# inverter-adc-demo.net
KiCad netlist of a schematic drawn in EAGLE
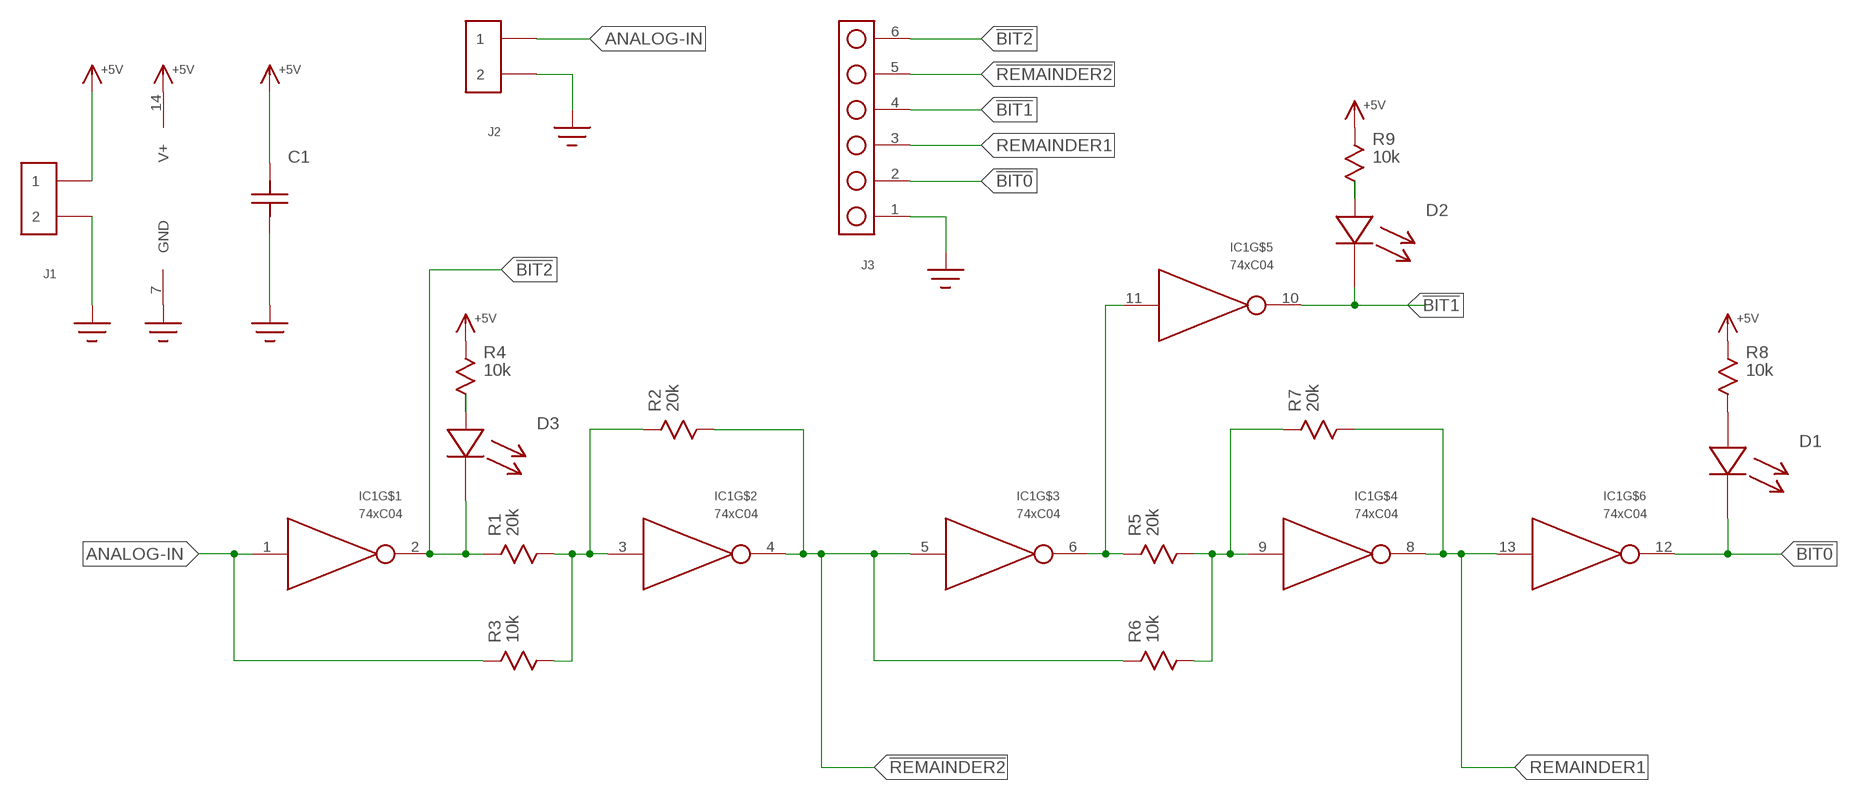
[diagram p0: schematic, sheet 1]

(export (version "E")
  (design (tool "Eeschema 10.0.6"))
  (components
    (comp (ref "C1")
      (value "C100MIL")
      (footprint "eagle-import:C-100MIL")
      (libsource (lib "eagle-import") (part "C100MIL"))
    )
    (comp (ref "D1")
      (value "LED5MM")
      (footprint "eagle-import:LED-5MM")
      (libsource (lib "eagle-import") (part "LED5MM"))
    )
    (comp (ref "D2")
      (value "LED5MM")
      (footprint "eagle-import:LED-5MM")
      (libsource (lib "eagle-import") (part "LED5MM"))
    )
    (comp (ref "D3")
      (value "LED5MM")
      (footprint "eagle-import:LED-5MM")
      (libsource (lib "eagle-import") (part "LED5MM"))
    )
    (comp (ref "IC1")
      (value "74xC04")
      (footprint "eagle-import:DIP14")
      (libsource (lib "eagle-import") (part "74XX04DIP"))
    )
    (comp (ref "J1")
      (value "HEADER_2PIN")
      (footprint "eagle-import:HEADER_2PIN")
      (libsource (lib "eagle-import") (part "HEADER_2PIN"))
    )
    (comp (ref "J2")
      (value "HEADER_2PIN")
      (footprint "eagle-import:HEADER_2PIN")
      (libsource (lib "eagle-import") (part "HEADER_2PIN"))
    )
    (comp (ref "J3")
      (value "HEADER_6PIN")
      (footprint "eagle-import:HEADER_6PIN")
      (libsource (lib "eagle-import") (part "HEADER_6PIN"))
    )
    (comp (ref "R1")
      (value "20k")
      (footprint "eagle-import:R-0.25W")
      (libsource (lib "eagle-import") (part "RTH-0.25W"))
    )
    (comp (ref "R2")
      (value "20k")
      (footprint "eagle-import:R-0.25W")
      (libsource (lib "eagle-import") (part "RTH-0.25W"))
    )
    (comp (ref "R3")
      (value "10k")
      (footprint "eagle-import:R-0.25W")
      (libsource (lib "eagle-import") (part "RTH-0.25W"))
    )
    (comp (ref "R4")
      (value "10k")
      (footprint "eagle-import:R-0.25W")
      (libsource (lib "eagle-import") (part "RTH-0.25W"))
    )
    (comp (ref "R5")
      (value "20k")
      (footprint "eagle-import:R-0.25W")
      (libsource (lib "eagle-import") (part "RTH-0.25W"))
    )
    (comp (ref "R6")
      (value "10k")
      (footprint "eagle-import:R-0.25W")
      (libsource (lib "eagle-import") (part "RTH-0.25W"))
    )
    (comp (ref "R7")
      (value "20k")
      (footprint "eagle-import:R-0.25W")
      (libsource (lib "eagle-import") (part "RTH-0.25W"))
    )
    (comp (ref "R8")
      (value "10k")
      (footprint "eagle-import:R-0.25W")
      (libsource (lib "eagle-import") (part "RTH-0.25W"))
    )
    (comp (ref "R9")
      (value "10k")
      (footprint "eagle-import:R-0.25W")
      (libsource (lib "eagle-import") (part "RTH-0.25W"))
    )
  )
  (nets
    (net (code "1") (name "+5V") (class "Default")
      (node (ref "C1") (pin "P$2") (pinfunction "P$2_P$2") (pintype "bidirectional"))
      (node (ref "IC1") (pin "14") (pinfunction "V+_14") (pintype "bidirectional"))
      (node (ref "J1") (pin "1") (pinfunction "1_1") (pintype "bidirectional"))
      (node (ref "R4") (pin "P$1") (pinfunction "P$3_P$1") (pintype "bidirectional"))
      (node (ref "R8") (pin "P$1") (pinfunction "P$3_P$1") (pintype "bidirectional"))
      (node (ref "R9") (pin "P$1") (pinfunction "P$3_P$1") (pintype "bidirectional"))
    )
    (net (code "2") (name "/~{BIT0}") (class "Default")
      (node (ref "D1") (pin "C") (pinfunction "C_C") (pintype "bidirectional"))
      (node (ref "IC1") (pin "12") (pinfunction "OUT_12") (pintype "bidirectional"))
      (node (ref "J3") (pin "2") (pinfunction "2_2") (pintype "bidirectional"))
    )
    (net (code "3") (name "/~{BIT1}") (class "Default")
      (node (ref "D2") (pin "C") (pinfunction "C_C") (pintype "bidirectional"))
      (node (ref "IC1") (pin "10") (pinfunction "OUT_10") (pintype "bidirectional"))
      (node (ref "J3") (pin "4") (pinfunction "4_4") (pintype "bidirectional"))
    )
    (net (code "4") (name "/~{BIT2}") (class "Default")
      (node (ref "D3") (pin "C") (pinfunction "C_C") (pintype "bidirectional"))
      (node (ref "IC1") (pin "2") (pinfunction "OUT_2") (pintype "bidirectional"))
      (node (ref "J3") (pin "6") (pinfunction "6_6") (pintype "bidirectional"))
      (node (ref "R1") (pin "P$1") (pinfunction "P$3_P$1") (pintype "bidirectional"))
    )
    (net (code "5") (name "/~{REMAINDER2}") (class "Default")
      (node (ref "IC1") (pin "4") (pinfunction "OUT_4") (pintype "bidirectional"))
      (node (ref "IC1") (pin "5") (pinfunction "IN_5") (pintype "bidirectional"))
      (node (ref "J3") (pin "5") (pinfunction "5_5") (pintype "bidirectional"))
      (node (ref "R2") (pin "P$2") (pinfunction "P$4_P$2") (pintype "bidirectional"))
      (node (ref "R6") (pin "P$1") (pinfunction "P$3_P$1") (pintype "bidirectional"))
    )
    (net (code "6") (name "ANALOG-IN") (class "Default")
      (node (ref "IC1") (pin "1") (pinfunction "IN_1") (pintype "bidirectional"))
      (node (ref "J2") (pin "1") (pinfunction "1_1") (pintype "bidirectional"))
      (node (ref "R3") (pin "P$1") (pinfunction "P$3_P$1") (pintype "bidirectional"))
    )
    (net (code "7") (name "GND") (class "Default")
      (node (ref "C1") (pin "P$1") (pinfunction "P$1_P$1") (pintype "bidirectional"))
      (node (ref "IC1") (pin "7") (pinfunction "GND_7") (pintype "bidirectional"))
      (node (ref "J1") (pin "2") (pinfunction "2_2") (pintype "bidirectional"))
      (node (ref "J2") (pin "2") (pinfunction "2_2") (pintype "bidirectional"))
      (node (ref "J3") (pin "1") (pinfunction "1_1") (pintype "bidirectional"))
    )
    (net (code "8") (name "Net-(IC1B-IN)") (class "Default")
      (node (ref "IC1") (pin "3") (pinfunction "IN_3") (pintype "bidirectional"))
      (node (ref "R1") (pin "P$2") (pinfunction "P$4_P$2") (pintype "bidirectional"))
      (node (ref "R2") (pin "P$1") (pinfunction "P$3_P$1") (pintype "bidirectional"))
      (node (ref "R3") (pin "P$2") (pinfunction "P$4_P$2") (pintype "bidirectional"))
    )
    (net (code "9") (name "Net-(IC1C-OUT)") (class "Default")
      (node (ref "IC1") (pin "11") (pinfunction "IN_11") (pintype "bidirectional"))
      (node (ref "IC1") (pin "6") (pinfunction "OUT_6") (pintype "bidirectional"))
      (node (ref "R5") (pin "P$1") (pinfunction "P$3_P$1") (pintype "bidirectional"))
    )
    (net (code "10") (name "Net-(IC1D-IN)") (class "Default")
      (node (ref "IC1") (pin "9") (pinfunction "IN_9") (pintype "bidirectional"))
      (node (ref "R5") (pin "P$2") (pinfunction "P$4_P$2") (pintype "bidirectional"))
      (node (ref "R6") (pin "P$2") (pinfunction "P$4_P$2") (pintype "bidirectional"))
      (node (ref "R7") (pin "P$1") (pinfunction "P$3_P$1") (pintype "bidirectional"))
    )
    (net (code "11") (name "Net-(R4-P$4)") (class "Default")
      (node (ref "D3") (pin "A") (pinfunction "A_A") (pintype "bidirectional"))
      (node (ref "R4") (pin "P$2") (pinfunction "P$4_P$2") (pintype "bidirectional"))
    )
    (net (code "12") (name "Net-(R8-P$4)") (class "Default")
      (node (ref "D1") (pin "A") (pinfunction "A_A") (pintype "bidirectional"))
      (node (ref "R8") (pin "P$2") (pinfunction "P$4_P$2") (pintype "bidirectional"))
    )
    (net (code "13") (name "Net-(R9-P$4)") (class "Default")
      (node (ref "D2") (pin "A") (pinfunction "A_A") (pintype "bidirectional"))
      (node (ref "R9") (pin "P$2") (pinfunction "P$4_P$2") (pintype "bidirectional"))
    )
    (net (code "14") (name "REMAINDER1") (class "Default")
      (node (ref "IC1") (pin "13") (pinfunction "IN_13") (pintype "bidirectional"))
      (node (ref "IC1") (pin "8") (pinfunction "OUT_8") (pintype "bidirectional"))
      (node (ref "J3") (pin "3") (pinfunction "3_3") (pintype "bidirectional"))
      (node (ref "R7") (pin "P$2") (pinfunction "P$4_P$2") (pintype "bidirectional"))
    )
  )
)
